# 4ch_constant_current_driver.net
KiCad netlist of a schematic drawn in EAGLE
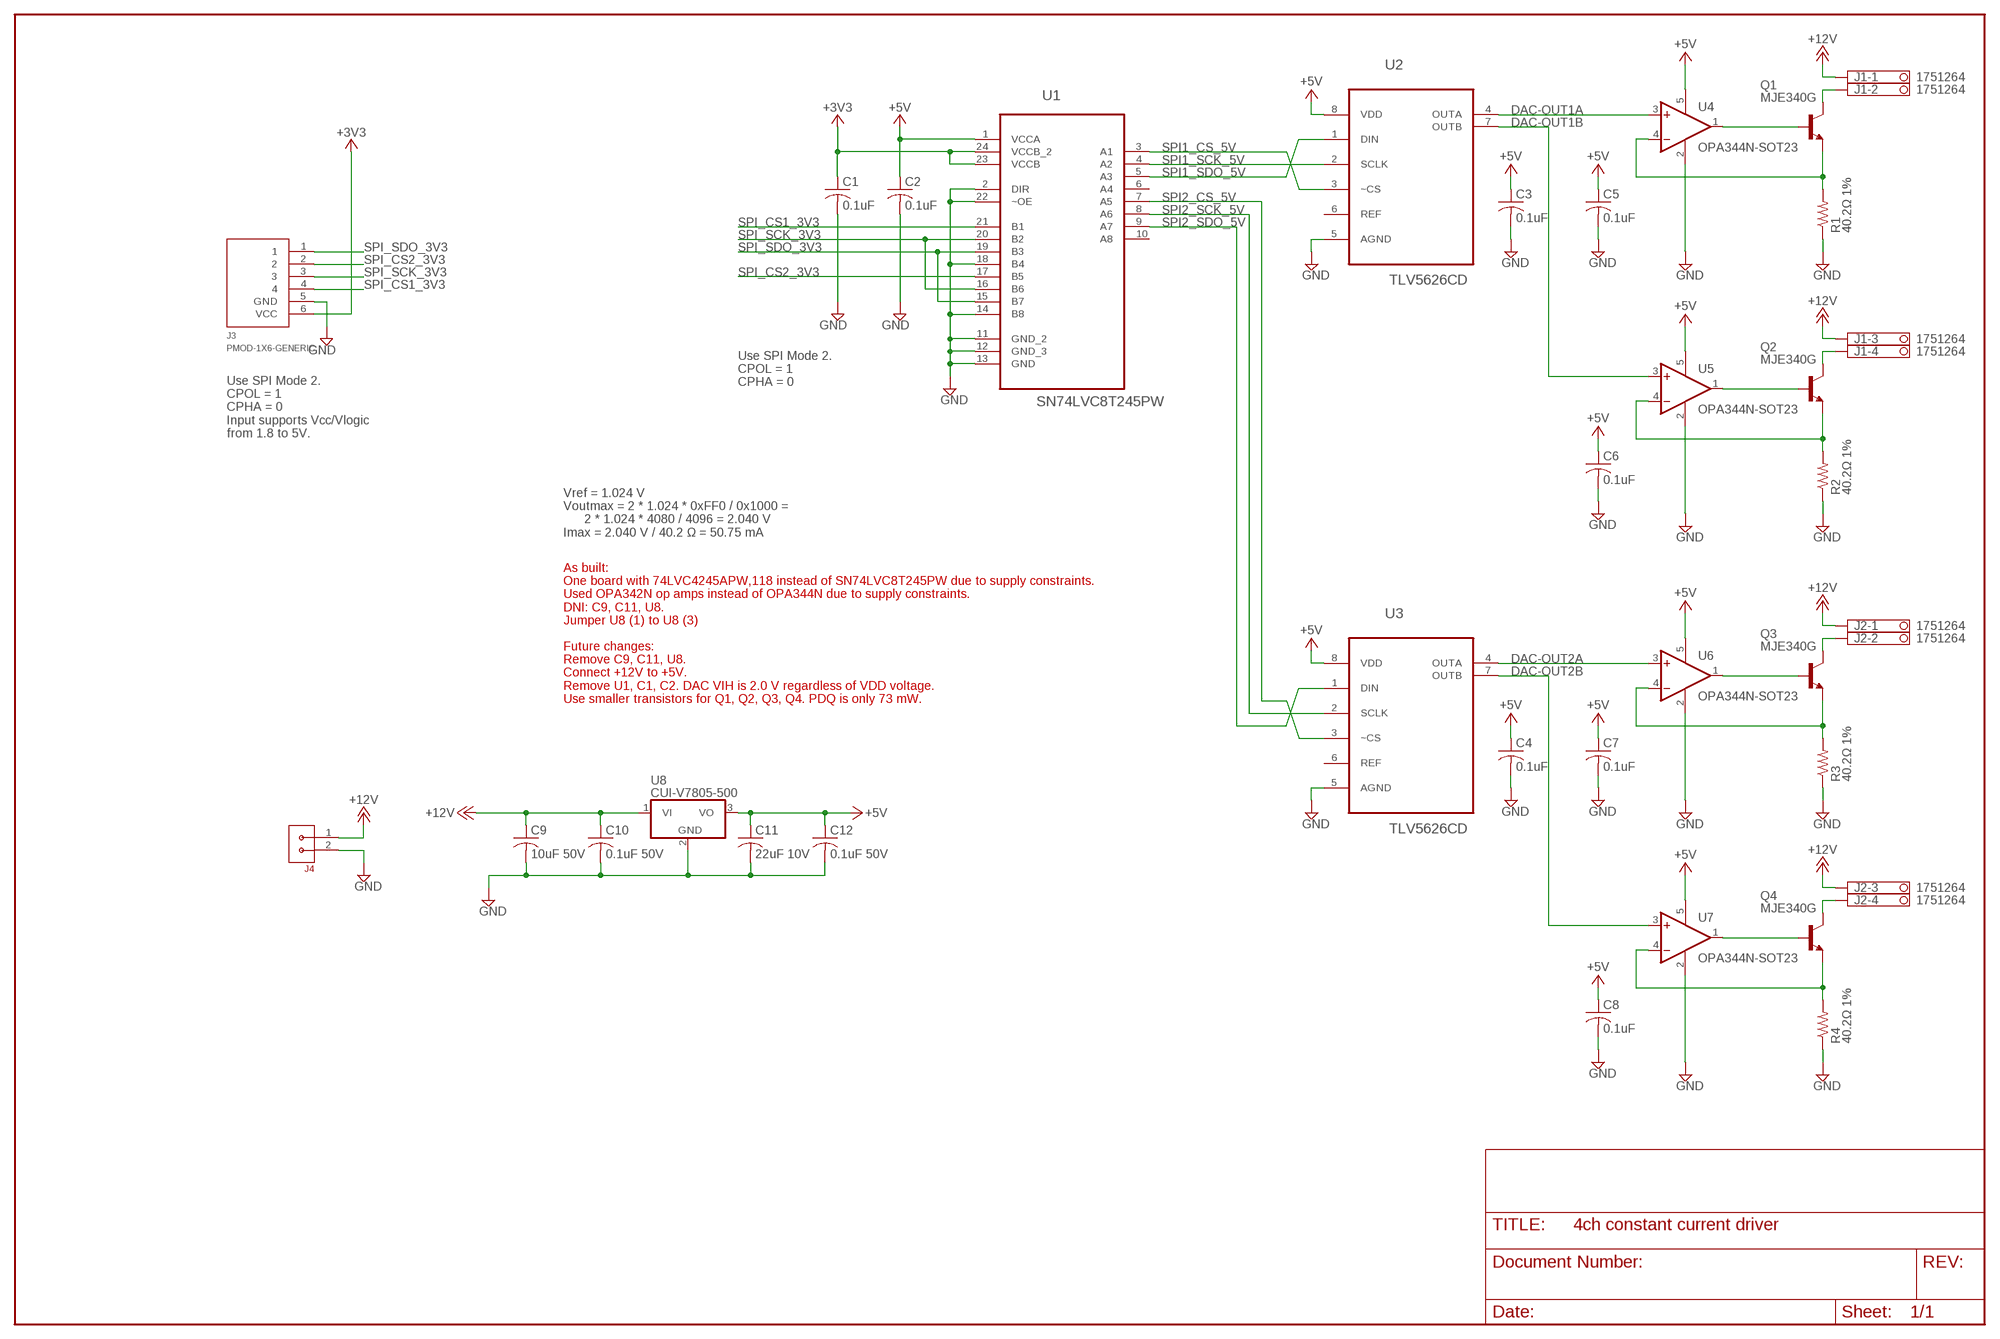
[diagram p0: schematic, sheet 1]

(export (version "E")
  (design (tool "Eeschema 10.0.6"))
  (components
    (comp (ref "C1")
      (value "0.1uF")
      (footprint "eagle-import:C0603K")
      (fields (field (name "MFR") "KEMET") (field (name "MFR_PART_NO") "C1206C104K5RACAUTO"))
      (libsource (lib "eagle-import") (part "C-USC0603K"))
    )
    (comp (ref "C2")
      (value "0.1uF")
      (footprint "eagle-import:C0603K")
      (fields (field (name "MFR") "KEMET") (field (name "MFR_PART_NO") "C1206C104K5RACAUTO"))
      (libsource (lib "eagle-import") (part "C-USC0603K"))
    )
    (comp (ref "C3")
      (value "0.1uF")
      (footprint "eagle-import:C0603K")
      (fields (field (name "MFR") "KEMET") (field (name "MFR_PART_NO") "C1206C104K5RACAUTO"))
      (libsource (lib "eagle-import") (part "C-USC0603K"))
    )
    (comp (ref "C4")
      (value "0.1uF")
      (footprint "eagle-import:C0603K")
      (fields (field (name "MFR") "KEMET") (field (name "MFR_PART_NO") "C1206C104K5RACAUTO"))
      (libsource (lib "eagle-import") (part "C-USC0603K"))
    )
    (comp (ref "C5")
      (value "0.1uF")
      (footprint "eagle-import:C0603K")
      (fields (field (name "MFR") "KEMET") (field (name "MFR_PART_NO") "C1206C104K5RACAUTO"))
      (libsource (lib "eagle-import") (part "C-USC0603K"))
    )
    (comp (ref "C6")
      (value "0.1uF")
      (footprint "eagle-import:C0603K")
      (fields (field (name "MFR") "KEMET") (field (name "MFR_PART_NO") "C1206C104K5RACAUTO"))
      (libsource (lib "eagle-import") (part "C-USC0603K"))
    )
    (comp (ref "C7")
      (value "0.1uF")
      (footprint "eagle-import:C0603K")
      (fields (field (name "MFR") "KEMET") (field (name "MFR_PART_NO") "C1206C104K5RACAUTO"))
      (libsource (lib "eagle-import") (part "C-USC0603K"))
    )
    (comp (ref "C8")
      (value "0.1uF")
      (footprint "eagle-import:C0603K")
      (fields (field (name "MFR") "KEMET") (field (name "MFR_PART_NO") "C1206C104K5RACAUTO"))
      (libsource (lib "eagle-import") (part "C-USC0603K"))
    )
    (comp (ref "C9")
      (value "10uF 50V")
      (footprint "eagle-import:C1210K")
      (fields (field (name "MFR") "KEMET") (field (name "MFR_PART_NO") "C1210C106K5RACTU"))
      (libsource (lib "eagle-import") (part "C-USC1210K"))
    )
    (comp (ref "C10")
      (value "0.1uF 50V")
      (footprint "eagle-import:C1206K")
      (fields (field (name "MFR") "KEMET") (field (name "MFR_PART_NO") "C1206S104M5RACTU"))
      (libsource (lib "eagle-import") (part "C-USC1206K"))
    )
    (comp (ref "C11")
      (value "22uF 10V")
      (footprint "eagle-import:C1206K")
      (fields (field (name "MFR") "KEMET") (field (name "MFR_PART_NO") "C1206C226K8RAC7800"))
      (libsource (lib "eagle-import") (part "C-USC1206K"))
    )
    (comp (ref "C12")
      (value "0.1uF 50V")
      (footprint "eagle-import:C1206K")
      (fields (field (name "MFR") "KEMET") (field (name "MFR_PART_NO") "C1206S104M5RACTU"))
      (libsource (lib "eagle-import") (part "C-USC1206K"))
    )
    (comp (ref "J1")
      (value "1751264")
      (footprint "eagle-import:1751264")
      (libsource (lib "eagle-import") (part "1751264"))
    )
    (comp (ref "J2")
      (value "1751264")
      (footprint "eagle-import:1751264")
      (libsource (lib "eagle-import") (part "1751264"))
    )
    (comp (ref "J3")
      (value "PMOD-1X6-GENERIC")
      (footprint "eagle-import:CON-PMOD-1X6")
      (libsource (lib "eagle-import") (part "PMOD-1X6-GENERIC"))
    )
    (comp (ref "J4")
      (value "CON-3.81MM-1X2-PHOENIX")
      (footprint "eagle-import:CON-PHOENIX-3.81-1X2-RA")
      (libsource (lib "eagle-import") (part "CON-3.81MM-1X2-PHOENIX"))
    )
    (comp (ref "Q1")
      (value "MJE340G")
      (footprint "eagle-import:TO126V")
      (fields (field (name "MFR") "ON SEMI"))
      (libsource (lib "eagle-import") (part "-NPN-TO126V"))
    )
    (comp (ref "Q2")
      (value "MJE340G")
      (footprint "eagle-import:TO126V")
      (fields (field (name "MFR") "ON SEMI"))
      (libsource (lib "eagle-import") (part "-NPN-TO126V"))
    )
    (comp (ref "Q3")
      (value "MJE340G")
      (footprint "eagle-import:TO126V")
      (fields (field (name "MFR") "ON SEMI"))
      (libsource (lib "eagle-import") (part "-NPN-TO126V"))
    )
    (comp (ref "Q4")
      (value "MJE340G")
      (footprint "eagle-import:TO126V")
      (fields (field (name "MFR") "ON SEMI"))
      (libsource (lib "eagle-import") (part "-NPN-TO126V"))
    )
    (comp (ref "R1")
      (value "40.2Ω 1%")
      (footprint "eagle-import:R1210")
      (fields (field (name "MFR") "PANASONIC") (field (name "MFR_PART_NO") "ERJ-14NF73R2U"))
      (libsource (lib "eagle-import") (part "R-US_R1210"))
    )
    (comp (ref "R2")
      (value "40.2Ω 1%")
      (footprint "eagle-import:R1210")
      (fields (field (name "MFR") "PANASONIC") (field (name "MFR_PART_NO") "ERJ-14NF73R2U"))
      (libsource (lib "eagle-import") (part "R-US_R1210"))
    )
    (comp (ref "R3")
      (value "40.2Ω 1%")
      (footprint "eagle-import:R1210")
      (fields (field (name "MFR") "PANASONIC") (field (name "MFR_PART_NO") "ERJ-14NF73R2U"))
      (libsource (lib "eagle-import") (part "R-US_R1210"))
    )
    (comp (ref "R4")
      (value "40.2Ω 1%")
      (footprint "eagle-import:R1210")
      (fields (field (name "MFR") "PANASONIC") (field (name "MFR_PART_NO") "ERJ-14NF73R2U"))
      (libsource (lib "eagle-import") (part "R-US_R1210"))
    )
    (comp (ref "U1")
      (value "SN74LVC8T245PW")
      (footprint "eagle-import:SOP65P640X120-24N")
      (fields (field (name "MPN") "SN74AVC8T245PW") (field (name "MFR") "TI"))
      (libsource (lib "eagle-import") (part "SN74AVC8T245PW"))
    )
    (comp (ref "U2")
      (value "TLV5626CD")
      (footprint "eagle-import:SOIC127P600X175-8N")
      (fields (field (name "MFR") "TI"))
      (libsource (lib "eagle-import") (part "TLV5626CD"))
    )
    (comp (ref "U3")
      (value "TLV5626CD")
      (footprint "eagle-import:SOIC127P600X175-8N")
      (fields (field (name "MFR") "TI"))
      (libsource (lib "eagle-import") (part "TLV5626CD"))
    )
    (comp (ref "U4")
      (value "OPA344N-SOT23")
      (footprint "eagle-import:SOT23-5")
      (fields (field (name "MFR") "TI") (field (name "MFR_PART_NO") "OPA344NA/3K"))
      (libsource (lib "eagle-import") (part "OPA-SOT23344N"))
    )
    (comp (ref "U5")
      (value "OPA344N-SOT23")
      (footprint "eagle-import:SOT23-5")
      (fields (field (name "MFR") "TI") (field (name "MFR_PART_NO") "OPA344NA/3K"))
      (libsource (lib "eagle-import") (part "OPA-SOT23344N"))
    )
    (comp (ref "U6")
      (value "OPA344N-SOT23")
      (footprint "eagle-import:SOT23-5")
      (fields (field (name "MFR") "TI") (field (name "MFR_PART_NO") "OPA344NA/3K"))
      (libsource (lib "eagle-import") (part "OPA-SOT23344N"))
    )
    (comp (ref "U7")
      (value "OPA344N-SOT23")
      (footprint "eagle-import:SOT23-5")
      (fields (field (name "MFR") "TI") (field (name "MFR_PART_NO") "OPA344NA/3K"))
      (libsource (lib "eagle-import") (part "OPA-SOT23344N"))
    )
    (comp (ref "U8")
      (value "CUI-V7805-500")
      (footprint "eagle-import:CUI-78XX-500")
      (libsource (lib "eagle-import") (part "CUI-V7803-500"))
    )
  )
  (nets
    (net (code "1") (name "+3V3") (class "Default")
      (node (ref "C1") (pin "1") (pinfunction "1_1") (pintype "passive"))
      (node (ref "J3") (pin "6") (pinfunction "VCC_6") (pintype "bidirectional"))
      (node (ref "U1") (pin "23") (pinfunction "VCCB_23") (pintype "power_in"))
      (node (ref "U1") (pin "24") (pinfunction "VCCB_2_24") (pintype "power_in"))
    )
    (net (code "2") (name "+5V") (class "Default")
      (node (ref "C11") (pin "1") (pinfunction "1_1") (pintype "passive"))
      (node (ref "C12") (pin "1") (pinfunction "1_1") (pintype "passive"))
      (node (ref "C2") (pin "1") (pinfunction "1_1") (pintype "passive"))
      (node (ref "C3") (pin "1") (pinfunction "1_1") (pintype "passive"))
      (node (ref "C4") (pin "1") (pinfunction "1_1") (pintype "passive"))
      (node (ref "C5") (pin "1") (pinfunction "1_1") (pintype "passive"))
      (node (ref "C6") (pin "1") (pinfunction "1_1") (pintype "passive"))
      (node (ref "C7") (pin "1") (pinfunction "1_1") (pintype "passive"))
      (node (ref "C8") (pin "1") (pinfunction "1_1") (pintype "passive"))
      (node (ref "U1") (pin "1") (pinfunction "VCCA_1") (pintype "power_in"))
      (node (ref "U2") (pin "8") (pinfunction "VDD_8") (pintype "power_in"))
      (node (ref "U3") (pin "8") (pinfunction "VDD_8") (pintype "power_in"))
      (node (ref "U4") (pin "5") (pinfunction "V+_5") (pintype "power_in"))
      (node (ref "U5") (pin "5") (pinfunction "V+_5") (pintype "power_in"))
      (node (ref "U6") (pin "5") (pinfunction "V+_5") (pintype "power_in"))
      (node (ref "U7") (pin "5") (pinfunction "V+_5") (pintype "power_in"))
      (node (ref "U8") (pin "3") (pinfunction "VO_3") (pintype "passive"))
    )
    (net (code "3") (name "+12V") (class "Default")
      (node (ref "C10") (pin "1") (pinfunction "1_1") (pintype "passive"))
      (node (ref "C9") (pin "1") (pinfunction "1_1") (pintype "passive"))
      (node (ref "J1") (pin "1") (pinfunction "K_1") (pintype "passive"))
      (node (ref "J1") (pin "3") (pinfunction "K_3") (pintype "passive"))
      (node (ref "J2") (pin "1") (pinfunction "K_1") (pintype "passive"))
      (node (ref "J2") (pin "3") (pinfunction "K_3") (pintype "passive"))
      (node (ref "J4") (pin "1") (pinfunction "1_1") (pintype "bidirectional"))
      (node (ref "U8") (pin "1") (pinfunction "VI_1") (pintype "input"))
    )
    (net (code "4") (name "/DAC-OUT1A") (class "Default")
      (node (ref "U2") (pin "4") (pinfunction "OUTA_4") (pintype "output"))
      (node (ref "U4") (pin "3") (pinfunction "+IN_3") (pintype "input"))
    )
    (net (code "5") (name "/DAC-OUT1B") (class "Default")
      (node (ref "U2") (pin "7") (pinfunction "OUTB_7") (pintype "output"))
      (node (ref "U5") (pin "3") (pinfunction "+IN_3") (pintype "input"))
    )
    (net (code "6") (name "/DAC-OUT2A") (class "Default")
      (node (ref "U3") (pin "4") (pinfunction "OUTA_4") (pintype "output"))
      (node (ref "U6") (pin "3") (pinfunction "+IN_3") (pintype "input"))
    )
    (net (code "7") (name "/DAC-OUT2B") (class "Default")
      (node (ref "U3") (pin "7") (pinfunction "OUTB_7") (pintype "output"))
      (node (ref "U7") (pin "3") (pinfunction "+IN_3") (pintype "input"))
    )
    (net (code "8") (name "/SPI1_CS_5V") (class "Default")
      (node (ref "U1") (pin "3") (pinfunction "A1_3") (pintype "bidirectional"))
      (node (ref "U2") (pin "3") (pinfunction "~{CS}_3") (pintype "input"))
    )
    (net (code "9") (name "/SPI1_SCK_5V") (class "Default")
      (node (ref "U1") (pin "4") (pinfunction "A2_4") (pintype "bidirectional"))
      (node (ref "U2") (pin "2") (pinfunction "SCLK_2") (pintype "input"))
    )
    (net (code "10") (name "/SPI1_SDO_5V") (class "Default")
      (node (ref "U1") (pin "5") (pinfunction "A3_5") (pintype "bidirectional"))
      (node (ref "U2") (pin "1") (pinfunction "DIN_1") (pintype "input"))
    )
    (net (code "11") (name "/SPI2_CS_5V") (class "Default")
      (node (ref "U1") (pin "7") (pinfunction "A5_7") (pintype "bidirectional"))
      (node (ref "U3") (pin "3") (pinfunction "~{CS}_3") (pintype "input"))
    )
    (net (code "12") (name "/SPI2_SCK_5V") (class "Default")
      (node (ref "U1") (pin "8") (pinfunction "A6_8") (pintype "bidirectional"))
      (node (ref "U3") (pin "2") (pinfunction "SCLK_2") (pintype "input"))
    )
    (net (code "13") (name "/SPI2_SDO_5V") (class "Default")
      (node (ref "U1") (pin "9") (pinfunction "A7_9") (pintype "bidirectional"))
      (node (ref "U3") (pin "1") (pinfunction "DIN_1") (pintype "input"))
    )
    (net (code "14") (name "/SPI_CS1_3V3") (class "Default")
      (node (ref "J3") (pin "4") (pinfunction "4_4") (pintype "bidirectional"))
      (node (ref "U1") (pin "21") (pinfunction "B1_21") (pintype "bidirectional"))
    )
    (net (code "15") (name "/SPI_CS2_3V3") (class "Default")
      (node (ref "J3") (pin "2") (pinfunction "2_2") (pintype "bidirectional"))
      (node (ref "U1") (pin "17") (pinfunction "B5_17") (pintype "bidirectional"))
    )
    (net (code "16") (name "/SPI_SCK_3V3") (class "Default")
      (node (ref "J3") (pin "3") (pinfunction "3_3") (pintype "bidirectional"))
      (node (ref "U1") (pin "16") (pinfunction "B6_16") (pintype "bidirectional"))
      (node (ref "U1") (pin "20") (pinfunction "B2_20") (pintype "bidirectional"))
    )
    (net (code "17") (name "/SPI_SDO_3V3") (class "Default")
      (node (ref "J3") (pin "1") (pinfunction "1_1") (pintype "bidirectional"))
      (node (ref "U1") (pin "15") (pinfunction "B7_15") (pintype "bidirectional"))
      (node (ref "U1") (pin "19") (pinfunction "B3_19") (pintype "bidirectional"))
    )
    (net (code "18") (name "GND") (class "Default")
      (node (ref "C1") (pin "2") (pinfunction "2_2") (pintype "passive"))
      (node (ref "C10") (pin "2") (pinfunction "2_2") (pintype "passive"))
      (node (ref "C11") (pin "2") (pinfunction "2_2") (pintype "passive"))
      (node (ref "C12") (pin "2") (pinfunction "2_2") (pintype "passive"))
      (node (ref "C2") (pin "2") (pinfunction "2_2") (pintype "passive"))
      (node (ref "C3") (pin "2") (pinfunction "2_2") (pintype "passive"))
      (node (ref "C4") (pin "2") (pinfunction "2_2") (pintype "passive"))
      (node (ref "C5") (pin "2") (pinfunction "2_2") (pintype "passive"))
      (node (ref "C6") (pin "2") (pinfunction "2_2") (pintype "passive"))
      (node (ref "C7") (pin "2") (pinfunction "2_2") (pintype "passive"))
      (node (ref "C8") (pin "2") (pinfunction "2_2") (pintype "passive"))
      (node (ref "C9") (pin "2") (pinfunction "2_2") (pintype "passive"))
      (node (ref "J3") (pin "5") (pinfunction "GND_5") (pintype "power_in"))
      (node (ref "J4") (pin "2") (pinfunction "2_2") (pintype "bidirectional"))
      (node (ref "R1") (pin "1") (pinfunction "1_1") (pintype "passive"))
      (node (ref "R2") (pin "1") (pinfunction "1_1") (pintype "passive"))
      (node (ref "R3") (pin "1") (pinfunction "1_1") (pintype "passive"))
      (node (ref "R4") (pin "1") (pinfunction "1_1") (pintype "passive"))
      (node (ref "U1") (pin "11") (pinfunction "GND_2_11") (pintype "passive"))
      (node (ref "U1") (pin "12") (pinfunction "GND_3_12") (pintype "passive"))
      (node (ref "U1") (pin "13") (pinfunction "GND_13") (pintype "passive"))
      (node (ref "U1") (pin "14") (pinfunction "B8_14") (pintype "bidirectional"))
      (node (ref "U1") (pin "18") (pinfunction "B4_18") (pintype "bidirectional"))
      (node (ref "U1") (pin "2") (pinfunction "DIR_2") (pintype "input"))
      (node (ref "U1") (pin "22") (pinfunction "~{OE}_22") (pintype "input"))
      (node (ref "U2") (pin "5") (pinfunction "AGND_5") (pintype "passive"))
      (node (ref "U3") (pin "5") (pinfunction "AGND_5") (pintype "passive"))
      (node (ref "U4") (pin "2") (pinfunction "V-_2") (pintype "power_in"))
      (node (ref "U5") (pin "2") (pinfunction "V-_2") (pintype "power_in"))
      (node (ref "U6") (pin "2") (pinfunction "V-_2") (pintype "power_in"))
      (node (ref "U7") (pin "2") (pinfunction "V-_2") (pintype "power_in"))
      (node (ref "U8") (pin "2") (pinfunction "GND_2") (pintype "passive"))
    )
    (net (code "19") (name "Net-(J1B-K)") (class "Default")
      (node (ref "J1") (pin "2") (pinfunction "K_2") (pintype "passive"))
      (node (ref "Q1") (pin "2") (pinfunction "C_2") (pintype "passive"))
    )
    (net (code "20") (name "Net-(J1D-K)") (class "Default")
      (node (ref "J1") (pin "4") (pinfunction "K_4") (pintype "passive"))
      (node (ref "Q2") (pin "2") (pinfunction "C_2") (pintype "passive"))
    )
    (net (code "21") (name "Net-(J2B-K)") (class "Default")
      (node (ref "J2") (pin "2") (pinfunction "K_2") (pintype "passive"))
      (node (ref "Q3") (pin "2") (pinfunction "C_2") (pintype "passive"))
    )
    (net (code "22") (name "Net-(J2D-K)") (class "Default")
      (node (ref "J2") (pin "4") (pinfunction "K_4") (pintype "passive"))
      (node (ref "Q4") (pin "2") (pinfunction "C_2") (pintype "passive"))
    )
    (net (code "23") (name "Net-(Q1-B)") (class "Default")
      (node (ref "Q1") (pin "3") (pinfunction "B_3") (pintype "passive"))
      (node (ref "U4") (pin "1") (pinfunction "OUT_1") (pintype "output"))
    )
    (net (code "24") (name "Net-(Q1-E)") (class "Default")
      (node (ref "Q1") (pin "1") (pinfunction "E_1") (pintype "passive"))
      (node (ref "R1") (pin "2") (pinfunction "2_2") (pintype "passive"))
      (node (ref "U4") (pin "4") (pinfunction "-IN_4") (pintype "input"))
    )
    (net (code "25") (name "Net-(Q2-B)") (class "Default")
      (node (ref "Q2") (pin "3") (pinfunction "B_3") (pintype "passive"))
      (node (ref "U5") (pin "1") (pinfunction "OUT_1") (pintype "output"))
    )
    (net (code "26") (name "Net-(Q2-E)") (class "Default")
      (node (ref "Q2") (pin "1") (pinfunction "E_1") (pintype "passive"))
      (node (ref "R2") (pin "2") (pinfunction "2_2") (pintype "passive"))
      (node (ref "U5") (pin "4") (pinfunction "-IN_4") (pintype "input"))
    )
    (net (code "27") (name "Net-(Q3-B)") (class "Default")
      (node (ref "Q3") (pin "3") (pinfunction "B_3") (pintype "passive"))
      (node (ref "U6") (pin "1") (pinfunction "OUT_1") (pintype "output"))
    )
    (net (code "28") (name "Net-(Q3-E)") (class "Default")
      (node (ref "Q3") (pin "1") (pinfunction "E_1") (pintype "passive"))
      (node (ref "R3") (pin "2") (pinfunction "2_2") (pintype "passive"))
      (node (ref "U6") (pin "4") (pinfunction "-IN_4") (pintype "input"))
    )
    (net (code "29") (name "Net-(Q4-B)") (class "Default")
      (node (ref "Q4") (pin "3") (pinfunction "B_3") (pintype "passive"))
      (node (ref "U7") (pin "1") (pinfunction "OUT_1") (pintype "output"))
    )
    (net (code "30") (name "Net-(Q4-E)") (class "Default")
      (node (ref "Q4") (pin "1") (pinfunction "E_1") (pintype "passive"))
      (node (ref "R4") (pin "2") (pinfunction "2_2") (pintype "passive"))
      (node (ref "U7") (pin "4") (pinfunction "-IN_4") (pintype "input"))
    )
    (net (code "31") (name "unconnected-(U1-A4-Pad6)") (class "Default")
      (node (ref "U1") (pin "6") (pinfunction "A4_6") (pintype "bidirectional"))
    )
    (net (code "32") (name "unconnected-(U1-A8-Pad10)") (class "Default")
      (node (ref "U1") (pin "10") (pinfunction "A8_10") (pintype "bidirectional"))
    )
    (net (code "33") (name "unconnected-(U2-REF-Pad6)") (class "Default")
      (node (ref "U2") (pin "6") (pinfunction "REF_6") (pintype "input"))
    )
    (net (code "34") (name "unconnected-(U3-REF-Pad6)") (class "Default")
      (node (ref "U3") (pin "6") (pinfunction "REF_6") (pintype "input"))
    )
  )
)
